# Sheet1.net
KiCad netlist of a schematic drawn in Altium Designer
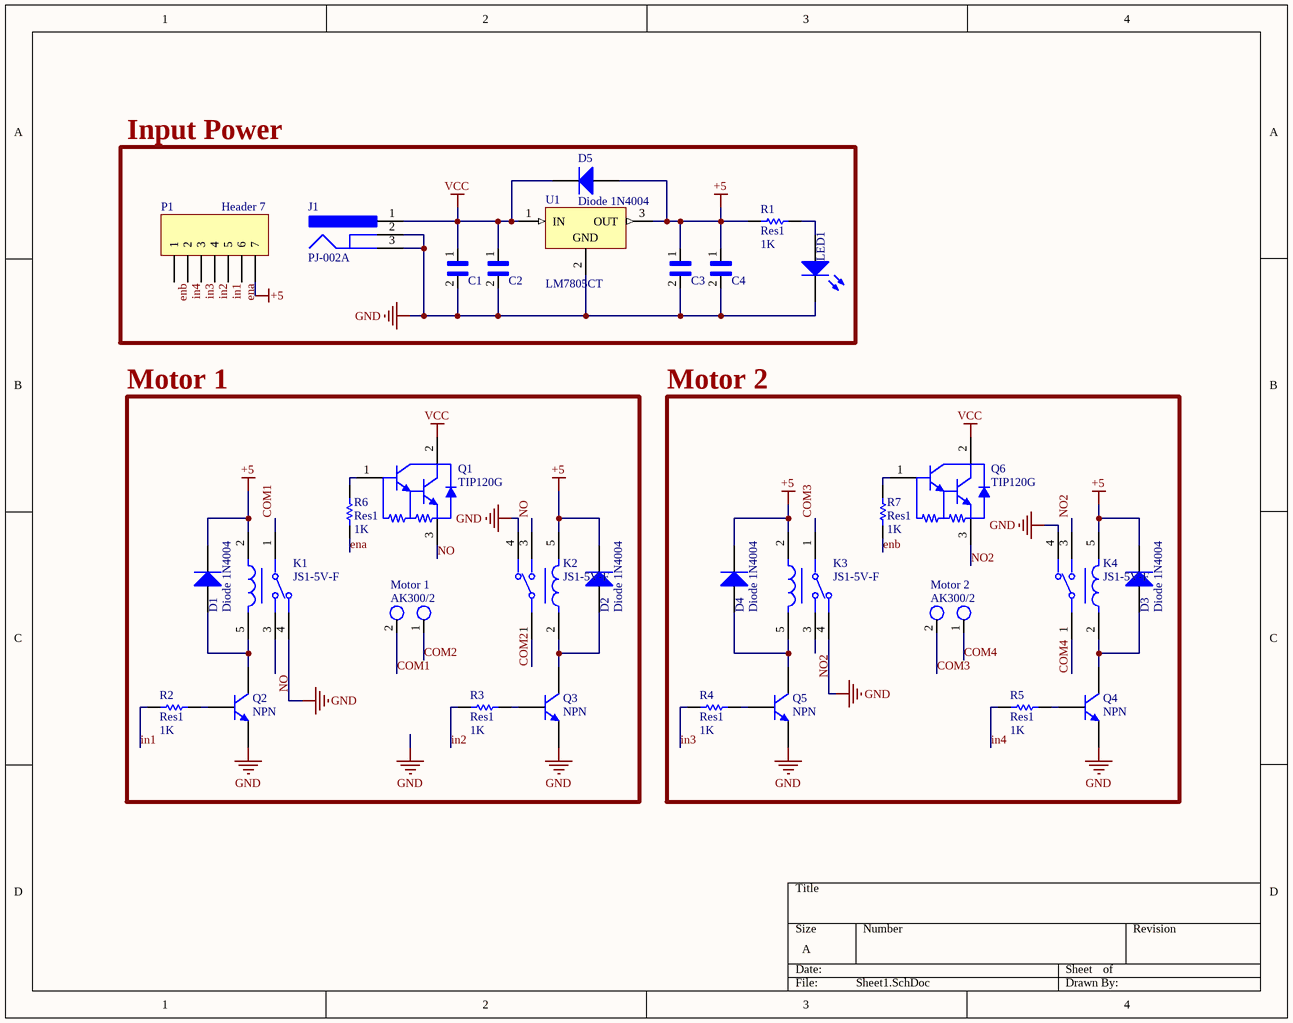
[diagram p0: Sheet1.SchDoc]

(export (version "E")
  (design (tool "Eeschema 10.0.6"))
  (components
    (comp (ref "C1")
      (value "RDE5C2A220J0M1H03A")
      (footprint "CAP_RDE5C2A220J0M1H03A")
      (description "Lead Capacitor C0G_EIA_ with Capacitance: 22pF and Rated Voltage: 100Vdc")
      (fields (field (name "MF") "Murata"))
      (libsource (lib "Schlib1") (part "RDE5C2A220J0M1H03A"))
    )
    (comp (ref "C2")
      (value "RDE5C2A220J0M1H03A")
      (footprint "CAP_RDE5C2A220J0M1H03A")
      (description "Lead Capacitor C0G_EIA_ with Capacitance: 22pF and Rated Voltage: 100Vdc")
      (fields (field (name "MF") "Murata"))
      (libsource (lib "Schlib1") (part "RDE5C2A220J0M1H03A"))
    )
    (comp (ref "C3")
      (value "RDE5C2A220J0M1H03A")
      (footprint "CAP_RDE5C2A220J0M1H03A")
      (description "Lead Capacitor C0G_EIA_ with Capacitance: 22pF and Rated Voltage: 100Vdc")
      (fields (field (name "MF") "Murata"))
      (libsource (lib "Schlib1") (part "RDE5C2A220J0M1H03A"))
    )
    (comp (ref "C4")
      (value "RDE5C2A220J0M1H03A")
      (footprint "CAP_RDE5C2A220J0M1H03A")
      (description "Lead Capacitor C0G_EIA_ with Capacitance: 22pF and Rated Voltage: 100Vdc")
      (fields (field (name "MF") "Murata"))
      (libsource (lib "Schlib1") (part "RDE5C2A220J0M1H03A"))
    )
    (comp (ref "D1")
      (value "Diode 1N4004")
      (footprint "DO-41")
      (description "1 Amp General Purpose Rectifier")
      (fields (field (name "PUBLISHER") "Altium Limited"))
      (libsource (lib "Miscellaneous Devices") (part "Diode 1N4004"))
    )
    (comp (ref "D2")
      (value "Diode 1N4004")
      (footprint "DO-41")
      (description "1 Amp General Purpose Rectifier")
      (fields (field (name "PUBLISHER") "Altium Limited"))
      (libsource (lib "Miscellaneous Devices") (part "Diode 1N4004"))
    )
    (comp (ref "D3")
      (value "Diode 1N4004")
      (footprint "DO-41")
      (description "1 Amp General Purpose Rectifier")
      (fields (field (name "PUBLISHER") "Altium Limited"))
      (libsource (lib "Miscellaneous Devices") (part "Diode 1N4004"))
    )
    (comp (ref "D4")
      (value "Diode 1N4004")
      (footprint "DO-41")
      (description "1 Amp General Purpose Rectifier")
      (fields (field (name "PUBLISHER") "Altium Limited"))
      (libsource (lib "Miscellaneous Devices") (part "Diode 1N4004"))
    )
    (comp (ref "D5")
      (value "Diode 1N4004")
      (footprint "DO-41")
      (description "1 Amp General Purpose Rectifier")
      (fields (field (name "PUBLISHER") "Altium Limited"))
      (libsource (lib "Miscellaneous Devices") (part "Diode 1N4004"))
    )
    (comp (ref "J1")
      (value "PJ-002A")
      (footprint "CUI-PJ-002A_V")
      (fields (field (name "MANUFACTURER") "CUIInc."))
      (libsource (lib "Schlib1") (part "CMP-2000-06895-1"))
    )
    (comp (ref "K1")
      (value "JS1-5V-F")
      (footprint "FP-JS1-5V-F-MFG")
      (description "RELAY GEN PURPOSE SPDT 10A 5V")
      (fields
        (field (name "OCTOPART") "https://octopart.com/js1-5v-f-panasonic-39428621")
        (field (name "MANUFACTURER") "Panasonic")
      )
      (libsource (lib "Altium Content Vault") (part "250623531296f86beaf95f2bc4a6d4c"))
    )
    (comp (ref "K2")
      (value "JS1-5V-F")
      (footprint "FP-JS1-5V-F-MFG")
      (description "RELAY GEN PURPOSE SPDT 10A 5V")
      (fields
        (field (name "OCTOPART") "https://octopart.com/js1-5v-f-panasonic-39428621")
        (field (name "MANUFACTURER") "Panasonic")
      )
      (libsource (lib "Altium Content Vault") (part "250623531296f86beaf95f2bc4a6d4c"))
    )
    (comp (ref "K3")
      (value "JS1-5V-F")
      (footprint "FP-JS1-5V-F-MFG")
      (description "RELAY GEN PURPOSE SPDT 10A 5V")
      (fields
        (field (name "OCTOPART") "https://octopart.com/js1-5v-f-panasonic-39428621")
        (field (name "MANUFACTURER") "Panasonic")
      )
      (libsource (lib "Altium Content Vault") (part "250623531296f86beaf95f2bc4a6d4c"))
    )
    (comp (ref "K4")
      (value "JS1-5V-F")
      (footprint "FP-JS1-5V-F-MFG")
      (description "RELAY GEN PURPOSE SPDT 10A 5V")
      (fields
        (field (name "OCTOPART") "https://octopart.com/js1-5v-f-panasonic-39428621")
        (field (name "MANUFACTURER") "Panasonic")
      )
      (libsource (lib "Altium Content Vault") (part "250623531296f86beaf95f2bc4a6d4c"))
    )
    (comp (ref "LED1")
      (value "151031SS06000")
      (footprint "Type 3mm")
      (description "THT LED round mono-color color lens, WL-TMRW, Super Red")
      (fields (field (name "MANUFACTURER") "Wuerth Elektronik"))
      (libsource (lib "Schlib1") (part "CMP-1488-00002-1"))
    )
    (comp (ref "Motor 1")
      (value "AK300/2")
      (footprint "AK300/2")
      (fields (field (name "MP") "AK300/3") (field (name "MF") "Altech"))
      (libsource (lib "Terminal Block - 2 Pins") (part "AK300/2"))
    )
    (comp (ref "Motor 2")
      (value "AK300/2")
      (footprint "AK300/2")
      (fields (field (name "MP") "AK300/3") (field (name "MF") "Altech"))
      (libsource (lib "Terminal Block - 2 Pins") (part "AK300/2"))
    )
    (comp (ref "P1")
      (value "Header 7")
      (footprint "HDR1X7")
      (description "Header, 7-Pin")
      (fields (field (name "PUBLISHER") "Altium Limited"))
      (libsource (lib "Miscellaneous Connectors") (part "Header 7"))
    )
    (comp (ref "Q1")
      (value "TIP120G")
      (footprint "ONSC-TO-220-3-221A-09")
      (description "Plastic Medium-Power, Complementary Silicon Transistor, 3-Pin TO-220, Pb-Free, Tube")
      (fields (field (name "MANUFACTURER") "On Semiconductor"))
      (libsource (lib "Altium Content Vault") (part "ONSC-DT-NPN-B1C2E3-3_A"))
    )
    (comp (ref "Q2")
      (value "NPN")
      (footprint "TO-226-AA")
      (description "NPN Bipolar Transistor")
      (fields (field (name "PUBLISHER") "Altium Limited"))
      (libsource (lib "Miscellaneous Devices") (part "NPN"))
    )
    (comp (ref "Q3")
      (value "NPN")
      (footprint "TO-226-AA")
      (description "NPN Bipolar Transistor")
      (fields (field (name "PUBLISHER") "Altium Limited"))
      (libsource (lib "Miscellaneous Devices") (part "NPN"))
    )
    (comp (ref "Q4")
      (value "NPN")
      (footprint "TO-226-AA")
      (description "NPN Bipolar Transistor")
      (fields (field (name "PUBLISHER") "Altium Limited"))
      (libsource (lib "Miscellaneous Devices") (part "NPN"))
    )
    (comp (ref "Q5")
      (value "NPN")
      (footprint "TO-226-AA")
      (description "NPN Bipolar Transistor")
      (fields (field (name "PUBLISHER") "Altium Limited"))
      (libsource (lib "Miscellaneous Devices") (part "NPN"))
    )
    (comp (ref "Q6")
      (value "TIP120G")
      (footprint "ONSC-TO-220-3-221A-09")
      (description "Plastic Medium-Power, Complementary Silicon Transistor, 3-Pin TO-220, Pb-Free, Tube")
      (fields (field (name "MANUFACTURER") "On Semiconductor"))
      (libsource (lib "Altium Content Vault") (part "ONSC-DT-NPN-B1C2E3-3_A"))
    )
    (comp (ref "R1")
      (value "Res1")
      (footprint "AXIAL-0.3")
      (description "Resistor")
      (fields (field (name "ALTIUM_VALUE") "1K") (field (name "PUBLISHER") "Altium Limited"))
      (libsource (lib "Miscellaneous Devices") (part "Res1"))
    )
    (comp (ref "R2")
      (value "Res1")
      (footprint "AXIAL-0.3")
      (description "Resistor")
      (fields (field (name "ALTIUM_VALUE") "1K") (field (name "PUBLISHER") "Altium Limited"))
      (libsource (lib "Miscellaneous Devices") (part "Res1"))
    )
    (comp (ref "R3")
      (value "Res1")
      (footprint "AXIAL-0.3")
      (description "Resistor")
      (fields (field (name "ALTIUM_VALUE") "1K") (field (name "PUBLISHER") "Altium Limited"))
      (libsource (lib "Miscellaneous Devices") (part "Res1"))
    )
    (comp (ref "R4")
      (value "Res1")
      (footprint "AXIAL-0.3")
      (description "Resistor")
      (fields (field (name "ALTIUM_VALUE") "1K") (field (name "PUBLISHER") "Altium Limited"))
      (libsource (lib "Miscellaneous Devices") (part "Res1"))
    )
    (comp (ref "R5")
      (value "Res1")
      (footprint "AXIAL-0.3")
      (description "Resistor")
      (fields (field (name "ALTIUM_VALUE") "1K") (field (name "PUBLISHER") "Altium Limited"))
      (libsource (lib "Miscellaneous Devices") (part "Res1"))
    )
    (comp (ref "R6")
      (value "Res1")
      (footprint "AXIAL-0.3")
      (description "Resistor")
      (fields (field (name "ALTIUM_VALUE") "1K") (field (name "PUBLISHER") "Altium Limited"))
      (libsource (lib "Miscellaneous Devices") (part "Res1"))
    )
    (comp (ref "R7")
      (value "Res1")
      (footprint "AXIAL-0.3")
      (description "Resistor")
      (fields (field (name "ALTIUM_VALUE") "1K") (field (name "PUBLISHER") "Altium Limited"))
      (libsource (lib "Miscellaneous Devices") (part "Res1"))
    )
    (comp (ref "U1")
      (value "LM7805CT")
      (footprint "FAIR-TO-220-3")
      (description "Positive Voltage Regulator, 5 V, 1 A, -40 to 125 degC, 3-Pin TO-220, RoHS, Tube")
      (fields (field (name "MANUFACTURER") "FairchildSemiconductor"))
      (libsource (lib "Schlib1") (part "CMP-2000-04938-1"))
    )
  )
  (nets
    (net (code "1") (name "+5") (class "Default")
      (node (ref "C3") (pin "1") (pinfunction "1_1") (pintype "passive"))
      (node (ref "C4") (pin "1") (pinfunction "1_1") (pintype "passive"))
      (node (ref "D1") (pin "2") (pinfunction "K_2") (pintype "passive"))
      (node (ref "D2") (pin "2") (pinfunction "K_2") (pintype "passive"))
      (node (ref "D3") (pin "2") (pinfunction "K_2") (pintype "passive"))
      (node (ref "D4") (pin "2") (pinfunction "K_2") (pintype "passive"))
      (node (ref "D5") (pin "1") (pinfunction "A_1") (pintype "passive"))
      (node (ref "K1") (pin "2") (pinfunction "1_COIL_2") (pintype "passive"))
      (node (ref "K2") (pin "5") (pinfunction "2_COIL_5") (pintype "passive"))
      (node (ref "K3") (pin "2") (pinfunction "1_COIL_2") (pintype "passive"))
      (node (ref "K4") (pin "5") (pinfunction "2_COIL_5") (pintype "passive"))
      (node (ref "P1") (pin "7") (pinfunction "7_7") (pintype "passive"))
      (node (ref "R1") (pin "1") (pinfunction "1_1") (pintype "passive"))
      (node (ref "U1") (pin "3") (pinfunction "OUT_3") (pintype "output"))
    )
    (net (code "2") (name "/COM1") (class "Default")
      (node (ref "K1") (pin "1") (pinfunction "COM_1") (pintype "passive"))
      (node (ref "Motor 1") (pin "2") (pinfunction "KL_2") (pintype "passive"))
    )
    (net (code "3") (name "/COM2") (class "Default")
      (node (ref "K2") (pin "1") (pinfunction "COM_1") (pintype "passive"))
      (node (ref "Motor 1") (pin "1") (pinfunction "KL_1") (pintype "passive"))
    )
    (net (code "4") (name "/COM3") (class "Default")
      (node (ref "K3") (pin "1") (pinfunction "COM_1") (pintype "passive"))
      (node (ref "Motor 2") (pin "2") (pinfunction "KL_2") (pintype "passive"))
    )
    (net (code "5") (name "/COM4") (class "Default")
      (node (ref "K4") (pin "1") (pinfunction "COM_1") (pintype "passive"))
      (node (ref "Motor 2") (pin "1") (pinfunction "KL_1") (pintype "passive"))
    )
    (net (code "6") (name "/NO") (class "Default")
      (node (ref "K1") (pin "3") (pinfunction "N.O._3") (pintype "passive"))
      (node (ref "K2") (pin "3") (pinfunction "N.O._3") (pintype "passive"))
      (node (ref "Q1") (pin "3") (pinfunction "E_3") (pintype "passive"))
    )
    (net (code "7") (name "/NO2") (class "Default")
      (node (ref "K3") (pin "3") (pinfunction "N.O._3") (pintype "passive"))
      (node (ref "K4") (pin "3") (pinfunction "N.O._3") (pintype "passive"))
      (node (ref "Q6") (pin "3") (pinfunction "E_3") (pintype "passive"))
    )
    (net (code "8") (name "/ena") (class "Default")
      (node (ref "P1") (pin "6") (pinfunction "6_6") (pintype "passive"))
      (node (ref "R6") (pin "1") (pinfunction "1_1") (pintype "passive"))
    )
    (net (code "9") (name "/enb") (class "Default")
      (node (ref "P1") (pin "1") (pinfunction "1_1") (pintype "passive"))
      (node (ref "R7") (pin "1") (pinfunction "1_1") (pintype "passive"))
    )
    (net (code "10") (name "/in1") (class "Default")
      (node (ref "P1") (pin "5") (pinfunction "5_5") (pintype "passive"))
      (node (ref "R2") (pin "1") (pinfunction "1_1") (pintype "passive"))
    )
    (net (code "11") (name "/in2") (class "Default")
      (node (ref "P1") (pin "4") (pinfunction "4_4") (pintype "passive"))
      (node (ref "R3") (pin "1") (pinfunction "1_1") (pintype "passive"))
    )
    (net (code "12") (name "/in3") (class "Default")
      (node (ref "P1") (pin "3") (pinfunction "3_3") (pintype "passive"))
      (node (ref "R4") (pin "1") (pinfunction "1_1") (pintype "passive"))
    )
    (net (code "13") (name "/in4") (class "Default")
      (node (ref "P1") (pin "2") (pinfunction "2_2") (pintype "passive"))
      (node (ref "R5") (pin "1") (pinfunction "1_1") (pintype "passive"))
    )
    (net (code "14") (name "GND") (class "Default")
      (node (ref "C1") (pin "2") (pinfunction "2_2") (pintype "passive"))
      (node (ref "C2") (pin "2") (pinfunction "2_2") (pintype "passive"))
      (node (ref "C3") (pin "2") (pinfunction "2_2") (pintype "passive"))
      (node (ref "C4") (pin "2") (pinfunction "2_2") (pintype "passive"))
      (node (ref "J1") (pin "2") (pinfunction "2_2") (pintype "passive"))
      (node (ref "J1") (pin "3") (pinfunction "3_3") (pintype "passive"))
      (node (ref "K1") (pin "4") (pinfunction "N.C._4") (pintype "passive"))
      (node (ref "K2") (pin "4") (pinfunction "N.C._4") (pintype "passive"))
      (node (ref "K3") (pin "4") (pinfunction "N.C._4") (pintype "passive"))
      (node (ref "K4") (pin "4") (pinfunction "N.C._4") (pintype "passive"))
      (node (ref "LED1") (pin "1") (pinfunction "K_1") (pintype "passive"))
      (node (ref "Q2") (pin "3") (pinfunction "E_3") (pintype "passive"))
      (node (ref "Q3") (pin "3") (pinfunction "E_3") (pintype "passive"))
      (node (ref "Q4") (pin "3") (pinfunction "E_3") (pintype "passive"))
      (node (ref "Q5") (pin "3") (pinfunction "E_3") (pintype "passive"))
      (node (ref "U1") (pin "2") (pinfunction "GND_2") (pintype "power_in"))
    )
    (net (code "15") (name "Net-(D1-A)") (class "Default")
      (node (ref "D1") (pin "1") (pinfunction "A_1") (pintype "passive"))
      (node (ref "K1") (pin "5") (pinfunction "2_COIL_5") (pintype "passive"))
      (node (ref "Q2") (pin "1") (pinfunction "C_1") (pintype "passive"))
    )
    (net (code "16") (name "Net-(D2-A)") (class "Default")
      (node (ref "D2") (pin "1") (pinfunction "A_1") (pintype "passive"))
      (node (ref "K2") (pin "2") (pinfunction "1_COIL_2") (pintype "passive"))
      (node (ref "Q3") (pin "1") (pinfunction "C_1") (pintype "passive"))
    )
    (net (code "17") (name "Net-(D3-A)") (class "Default")
      (node (ref "D3") (pin "1") (pinfunction "A_1") (pintype "passive"))
      (node (ref "K4") (pin "2") (pinfunction "1_COIL_2") (pintype "passive"))
      (node (ref "Q4") (pin "1") (pinfunction "C_1") (pintype "passive"))
    )
    (net (code "18") (name "Net-(D4-A)") (class "Default")
      (node (ref "D4") (pin "1") (pinfunction "A_1") (pintype "passive"))
      (node (ref "K3") (pin "5") (pinfunction "2_COIL_5") (pintype "passive"))
      (node (ref "Q5") (pin "1") (pinfunction "C_1") (pintype "passive"))
    )
    (net (code "19") (name "Net-(LED1-A)") (class "Default")
      (node (ref "LED1") (pin "2") (pinfunction "A_2") (pintype "passive"))
      (node (ref "R1") (pin "2") (pinfunction "2_2") (pintype "passive"))
    )
    (net (code "20") (name "Net-(Q1-B)") (class "Default")
      (node (ref "Q1") (pin "1") (pinfunction "B_1") (pintype "passive"))
      (node (ref "R6") (pin "2") (pinfunction "2_2") (pintype "passive"))
    )
    (net (code "21") (name "Net-(Q2-B)") (class "Default")
      (node (ref "Q2") (pin "2") (pinfunction "B_2") (pintype "passive"))
      (node (ref "R2") (pin "2") (pinfunction "2_2") (pintype "passive"))
    )
    (net (code "22") (name "Net-(Q3-B)") (class "Default")
      (node (ref "Q3") (pin "2") (pinfunction "B_2") (pintype "passive"))
      (node (ref "R3") (pin "2") (pinfunction "2_2") (pintype "passive"))
    )
    (net (code "23") (name "Net-(Q4-B)") (class "Default")
      (node (ref "Q4") (pin "2") (pinfunction "B_2") (pintype "passive"))
      (node (ref "R5") (pin "2") (pinfunction "2_2") (pintype "passive"))
    )
    (net (code "24") (name "Net-(Q5-B)") (class "Default")
      (node (ref "Q5") (pin "2") (pinfunction "B_2") (pintype "passive"))
      (node (ref "R4") (pin "2") (pinfunction "2_2") (pintype "passive"))
    )
    (net (code "25") (name "Net-(Q6-B)") (class "Default")
      (node (ref "Q6") (pin "1") (pinfunction "B_1") (pintype "passive"))
      (node (ref "R7") (pin "2") (pinfunction "2_2") (pintype "passive"))
    )
    (net (code "26") (name "VCC") (class "Default")
      (node (ref "C1") (pin "1") (pinfunction "1_1") (pintype "passive"))
      (node (ref "C2") (pin "1") (pinfunction "1_1") (pintype "passive"))
      (node (ref "D5") (pin "2") (pinfunction "K_2") (pintype "passive"))
      (node (ref "J1") (pin "1") (pinfunction "1_1") (pintype "passive"))
      (node (ref "Q1") (pin "2") (pinfunction "C_2") (pintype "passive"))
      (node (ref "Q6") (pin "2") (pinfunction "C_2") (pintype "passive"))
      (node (ref "U1") (pin "1") (pinfunction "IN_1") (pintype "input"))
    )
  )
)
